# AD8232_Heart_Rate_Monitor_v10.net
KiCad netlist of a schematic drawn in EAGLE
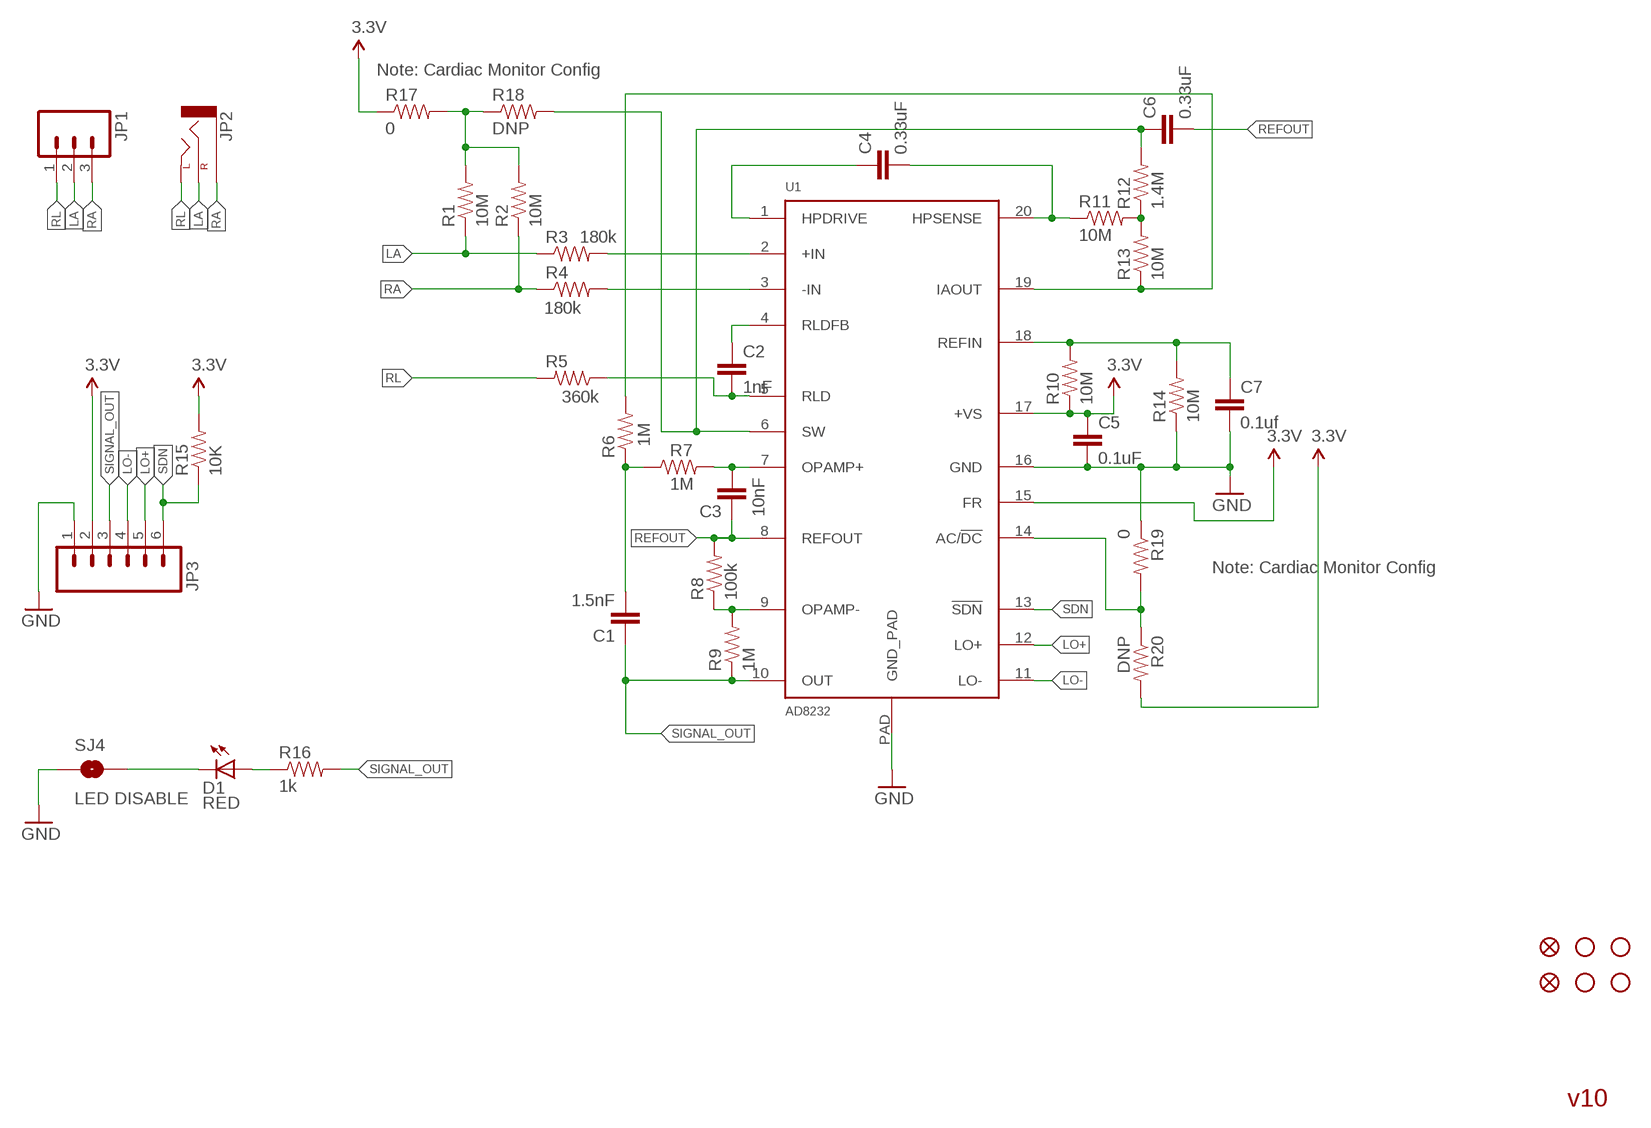
[diagram p0: schematic, sheet 1]

(export (version "E")
  (design (tool "Eeschema 10.0.6"))
  (components
    (comp (ref "C1")
      (value "1.5nF")
      (footprint "eagle-import:0603-CAP")
      (libsource (lib "eagle-import") (part "CAP0603-CAP"))
    )
    (comp (ref "C2")
      (value "1nF")
      (footprint "eagle-import:0603-CAP")
      (libsource (lib "eagle-import") (part "CAP0603-CAP"))
    )
    (comp (ref "C3")
      (value "10nF")
      (footprint "eagle-import:0603-CAP")
      (libsource (lib "eagle-import") (part "CAP0603-CAP"))
    )
    (comp (ref "C4")
      (value "0.33uF")
      (footprint "eagle-import:0805")
      (libsource (lib "eagle-import") (part "CAP0805"))
    )
    (comp (ref "C5")
      (value "0.1uF")
      (footprint "eagle-import:0603-CAP")
      (libsource (lib "eagle-import") (part "CAP0603-CAP"))
    )
    (comp (ref "C6")
      (value "0.33uF")
      (footprint "eagle-import:0805")
      (libsource (lib "eagle-import") (part "CAP0805"))
    )
    (comp (ref "C7")
      (value "0.1uf")
      (footprint "eagle-import:0603-CAP")
      (libsource (lib "eagle-import") (part "CAP0603-CAP"))
    )
    (comp (ref "D1")
      (value "RED")
      (footprint "eagle-import:LED-0603")
      (libsource (lib "eagle-import") (part "LED-RED0603"))
    )
    (comp (ref "FID1")
      (value "FIDUCIAL1X2")
      (footprint "eagle-import:FIDUCIAL-1X2")
      (libsource (lib "eagle-import") (part "FIDUCIAL1X2"))
    )
    (comp (ref "FID2")
      (value "FIDUCIAL1X2")
      (footprint "eagle-import:FIDUCIAL-1X2")
      (libsource (lib "eagle-import") (part "FIDUCIAL1X2"))
    )
    (comp (ref "JP1")
      (value "M03PTH")
      (footprint "eagle-import:1X03")
      (libsource (lib "eagle-import") (part "M03PTH"))
    )
    (comp (ref "JP2")
      (value "AUDIO-JACKSMD2")
      (footprint "eagle-import:AUDIO-JACK-3.5MM-SMD")
      (libsource (lib "eagle-import") (part "AUDIO-JACKSMD2"))
    )
    (comp (ref "JP3")
      (value "M06SIP")
      (footprint "eagle-import:1X06")
      (libsource (lib "eagle-import") (part "M06SIP"))
    )
    (comp (ref "R1")
      (value "10M")
      (footprint "eagle-import:0603-RES")
      (libsource (lib "eagle-import") (part "RESISTOR0603-RES"))
    )
    (comp (ref "R2")
      (value "10M")
      (footprint "eagle-import:0603-RES")
      (libsource (lib "eagle-import") (part "RESISTOR0603-RES"))
    )
    (comp (ref "R3")
      (value "180k")
      (footprint "eagle-import:0603-RES")
      (libsource (lib "eagle-import") (part "RESISTOR0603-RES"))
    )
    (comp (ref "R4")
      (value "180k")
      (footprint "eagle-import:0603-RES")
      (libsource (lib "eagle-import") (part "RESISTOR0603-RES"))
    )
    (comp (ref "R5")
      (value "360k")
      (footprint "eagle-import:0603-RES")
      (libsource (lib "eagle-import") (part "RESISTOR0603-RES"))
    )
    (comp (ref "R6")
      (value "1M")
      (footprint "eagle-import:0603-RES")
      (libsource (lib "eagle-import") (part "RESISTOR0603-RES"))
    )
    (comp (ref "R7")
      (value "1M")
      (footprint "eagle-import:0603-RES")
      (libsource (lib "eagle-import") (part "RESISTOR0603-RES"))
    )
    (comp (ref "R8")
      (value "100k")
      (footprint "eagle-import:0603-RES")
      (libsource (lib "eagle-import") (part "RESISTOR0603-RES"))
    )
    (comp (ref "R9")
      (value "1M")
      (footprint "eagle-import:0603-RES")
      (libsource (lib "eagle-import") (part "RESISTOR0603-RES"))
    )
    (comp (ref "R10")
      (value "10M")
      (footprint "eagle-import:0603-RES")
      (libsource (lib "eagle-import") (part "RESISTOR0603-RES"))
    )
    (comp (ref "R11")
      (value "10M")
      (footprint "eagle-import:0603-RES")
      (libsource (lib "eagle-import") (part "RESISTOR0603-RES"))
    )
    (comp (ref "R12")
      (value "1.4M")
      (footprint "eagle-import:0603-RES")
      (libsource (lib "eagle-import") (part "RESISTOR0603-RES"))
    )
    (comp (ref "R13")
      (value "10M")
      (footprint "eagle-import:0603-RES")
      (libsource (lib "eagle-import") (part "RESISTOR0603-RES"))
    )
    (comp (ref "R14")
      (value "10M")
      (footprint "eagle-import:0603-RES")
      (libsource (lib "eagle-import") (part "RESISTOR0603-RES"))
    )
    (comp (ref "R15")
      (value "10K")
      (footprint "eagle-import:0603-RES")
      (libsource (lib "eagle-import") (part "10KOHM1/10W1%(0603)0603"))
    )
    (comp (ref "R16")
      (value "1k")
      (footprint "eagle-import:0603-RES")
      (libsource (lib "eagle-import") (part "1K-1%"))
    )
    (comp (ref "R17")
      (value "0")
      (footprint "eagle-import:0603")
      (libsource (lib "eagle-import") (part "0OHM1/10W5%(0603)"))
    )
    (comp (ref "R18")
      (value "DNP")
      (footprint "eagle-import:0603")
      (libsource (lib "eagle-import") (part "0OHM1/10W5%(0603)"))
    )
    (comp (ref "R19")
      (value "0")
      (footprint "eagle-import:0603")
      (libsource (lib "eagle-import") (part "0OHM1/10W5%(0603)"))
    )
    (comp (ref "R20")
      (value "DNP")
      (footprint "eagle-import:0603")
      (libsource (lib "eagle-import") (part "0OHM1/10W5%(0603)"))
    )
    (comp (ref "SJ4")
      (value "LED DISABLE")
      (footprint "eagle-import:SJ_2S-TRACE")
      (libsource (lib "eagle-import") (part "SOLDERJUMPERTRACE"))
    )
    (comp (ref "STANDOFF1")
      (value "STAND-OFF")
      (footprint "eagle-import:STAND-OFF")
      (libsource (lib "eagle-import") (part "STAND-OFF"))
    )
    (comp (ref "STANDOFF2")
      (value "STAND-OFF")
      (footprint "eagle-import:STAND-OFF")
      (libsource (lib "eagle-import") (part "STAND-OFF"))
    )
    (comp (ref "STANDOFF3")
      (value "STAND-OFF")
      (footprint "eagle-import:STAND-OFF")
      (libsource (lib "eagle-import") (part "STAND-OFF"))
    )
    (comp (ref "STANDOFF4")
      (value "STAND-OFF")
      (footprint "eagle-import:STAND-OFF")
      (libsource (lib "eagle-import") (part "STAND-OFF"))
    )
    (comp (ref "U1")
      (value "AD8232")
      (footprint "eagle-import:LFCSP_20")
      (libsource (lib "eagle-import") (part "AD8232"))
    )
  )
  (nets
    (net (code "1") (name "3.3V") (class "Default")
      (node (ref "C5") (pin "1") (pinfunction "1_1") (pintype "passive"))
      (node (ref "JP3") (pin "2") (pinfunction "2_2") (pintype "passive"))
      (node (ref "R10") (pin "1") (pinfunction "1_1") (pintype "passive"))
      (node (ref "R15") (pin "2") (pinfunction "2_2") (pintype "passive"))
      (node (ref "R17") (pin "1") (pinfunction "1_1") (pintype "passive"))
      (node (ref "R20") (pin "2") (pinfunction "2_2") (pintype "passive"))
      (node (ref "U1") (pin "15") (pinfunction "FR_15") (pintype "bidirectional"))
      (node (ref "U1") (pin "17") (pinfunction "+VS_17") (pintype "bidirectional"))
    )
    (net (code "2") (name "GND") (class "Default")
      (node (ref "C5") (pin "2") (pinfunction "2_2") (pintype "passive"))
      (node (ref "C7") (pin "2") (pinfunction "2_2") (pintype "passive"))
      (node (ref "JP3") (pin "1") (pinfunction "1_1") (pintype "passive"))
      (node (ref "R14") (pin "1") (pinfunction "1_1") (pintype "passive"))
      (node (ref "R19") (pin "1") (pinfunction "1_1") (pintype "passive"))
      (node (ref "SJ4") (pin "1") (pinfunction "1_1") (pintype "passive"))
      (node (ref "U1") (pin "16") (pinfunction "GND_16") (pintype "bidirectional"))
      (node (ref "U1") (pin "PAD") (pinfunction "GND_PAD_PAD") (pintype "bidirectional"))
    )
    (net (code "3") (name "LA") (class "Default")
      (node (ref "JP1") (pin "2") (pinfunction "2_2") (pintype "passive"))
      (node (ref "JP2") (pin "RING") (pinfunction "RIGHT_RING") (pintype "bidirectional"))
      (node (ref "R1") (pin "1") (pinfunction "1_1") (pintype "passive"))
      (node (ref "R3") (pin "1") (pinfunction "1_1") (pintype "passive"))
    )
    (net (code "4") (name "LO+") (class "Default")
      (node (ref "JP3") (pin "5") (pinfunction "5_5") (pintype "passive"))
      (node (ref "U1") (pin "12") (pinfunction "LO+_12") (pintype "bidirectional"))
    )
    (net (code "5") (name "LO-") (class "Default")
      (node (ref "JP3") (pin "4") (pinfunction "4_4") (pintype "passive"))
      (node (ref "U1") (pin "11") (pinfunction "LO-_11") (pintype "bidirectional"))
    )
    (net (code "6") (name "Net-(C1-Pad2)") (class "Default")
      (node (ref "C1") (pin "2") (pinfunction "2_2") (pintype "passive"))
      (node (ref "R6") (pin "1") (pinfunction "1_1") (pintype "passive"))
      (node (ref "R7") (pin "1") (pinfunction "1_1") (pintype "passive"))
    )
    (net (code "7") (name "Net-(D1-PadA)") (class "Default")
      (node (ref "D1") (pin "A") (pinfunction "A_A") (pintype "passive"))
      (node (ref "R16") (pin "1") (pinfunction "1_1") (pintype "passive"))
    )
    (net (code "8") (name "Net-(D1-PadC)") (class "Default")
      (node (ref "D1") (pin "C") (pinfunction "C_C") (pintype "passive"))
      (node (ref "SJ4") (pin "2") (pinfunction "2_2") (pintype "passive"))
    )
    (net (code "9") (name "Net-(R1-Pad2)") (class "Default")
      (node (ref "R1") (pin "2") (pinfunction "2_2") (pintype "passive"))
      (node (ref "R17") (pin "2") (pinfunction "2_2") (pintype "passive"))
      (node (ref "R18") (pin "1") (pinfunction "1_1") (pintype "passive"))
      (node (ref "R2") (pin "2") (pinfunction "2_2") (pintype "passive"))
    )
    (net (code "10") (name "Net-(R11-Pad2)") (class "Default")
      (node (ref "R11") (pin "2") (pinfunction "2_2") (pintype "passive"))
      (node (ref "R12") (pin "1") (pinfunction "1_1") (pintype "passive"))
      (node (ref "R13") (pin "2") (pinfunction "2_2") (pintype "passive"))
    )
    (net (code "11") (name "Net-(U1-+IN)") (class "Default")
      (node (ref "R3") (pin "2") (pinfunction "2_2") (pintype "passive"))
      (node (ref "U1") (pin "2") (pinfunction "+IN_2") (pintype "bidirectional"))
    )
    (net (code "12") (name "Net-(U1--IN)") (class "Default")
      (node (ref "R4") (pin "2") (pinfunction "2_2") (pintype "passive"))
      (node (ref "U1") (pin "3") (pinfunction "-IN_3") (pintype "bidirectional"))
    )
    (net (code "13") (name "Net-(U1-AC{slash}~{DC})") (class "Default")
      (node (ref "R19") (pin "2") (pinfunction "2_2") (pintype "passive"))
      (node (ref "R20") (pin "1") (pinfunction "1_1") (pintype "passive"))
      (node (ref "U1") (pin "14") (pinfunction "AC/~{DC}_14") (pintype "bidirectional"))
    )
    (net (code "14") (name "Net-(U1-HPDRIVE)") (class "Default")
      (node (ref "C4") (pin "1") (pinfunction "1_1") (pintype "passive"))
      (node (ref "U1") (pin "1") (pinfunction "HPDRIVE_1") (pintype "bidirectional"))
    )
    (net (code "15") (name "Net-(U1-HPSENSE)") (class "Default")
      (node (ref "C4") (pin "2") (pinfunction "2_2") (pintype "passive"))
      (node (ref "R11") (pin "1") (pinfunction "1_1") (pintype "passive"))
      (node (ref "U1") (pin "20") (pinfunction "HPSENSE_20") (pintype "bidirectional"))
    )
    (net (code "16") (name "Net-(U1-IAOUT)") (class "Default")
      (node (ref "R13") (pin "1") (pinfunction "1_1") (pintype "passive"))
      (node (ref "R6") (pin "2") (pinfunction "2_2") (pintype "passive"))
      (node (ref "U1") (pin "19") (pinfunction "IAOUT_19") (pintype "bidirectional"))
    )
    (net (code "17") (name "Net-(U1-OPAMP+)") (class "Default")
      (node (ref "C3") (pin "2") (pinfunction "2_2") (pintype "passive"))
      (node (ref "R7") (pin "2") (pinfunction "2_2") (pintype "passive"))
      (node (ref "U1") (pin "7") (pinfunction "OPAMP+_7") (pintype "bidirectional"))
    )
    (net (code "18") (name "Net-(U1-OPAMP-)") (class "Default")
      (node (ref "R8") (pin "1") (pinfunction "1_1") (pintype "passive"))
      (node (ref "R9") (pin "2") (pinfunction "2_2") (pintype "passive"))
      (node (ref "U1") (pin "9") (pinfunction "OPAMP-_9") (pintype "bidirectional"))
    )
    (net (code "19") (name "Net-(U1-REFIN)") (class "Default")
      (node (ref "C7") (pin "1") (pinfunction "1_1") (pintype "passive"))
      (node (ref "R10") (pin "2") (pinfunction "2_2") (pintype "passive"))
      (node (ref "R14") (pin "2") (pinfunction "2_2") (pintype "passive"))
      (node (ref "U1") (pin "18") (pinfunction "REFIN_18") (pintype "bidirectional"))
    )
    (net (code "20") (name "Net-(U1-RLD)") (class "Default")
      (node (ref "C2") (pin "2") (pinfunction "2_2") (pintype "passive"))
      (node (ref "R5") (pin "1") (pinfunction "1_1") (pintype "passive"))
      (node (ref "U1") (pin "5") (pinfunction "RLD_5") (pintype "bidirectional"))
    )
    (net (code "21") (name "Net-(U1-RLDFB)") (class "Default")
      (node (ref "C2") (pin "1") (pinfunction "1_1") (pintype "passive"))
      (node (ref "U1") (pin "4") (pinfunction "RLDFB_4") (pintype "bidirectional"))
    )
    (net (code "22") (name "Net-(U1-SW)") (class "Default")
      (node (ref "C6") (pin "1") (pinfunction "1_1") (pintype "passive"))
      (node (ref "R12") (pin "2") (pinfunction "2_2") (pintype "passive"))
      (node (ref "R18") (pin "2") (pinfunction "2_2") (pintype "passive"))
      (node (ref "U1") (pin "6") (pinfunction "SW_6") (pintype "bidirectional"))
    )
    (net (code "23") (name "RA") (class "Default")
      (node (ref "JP1") (pin "3") (pinfunction "3_3") (pintype "passive"))
      (node (ref "JP2") (pin "SLEEVE") (pinfunction "SLEEVE_SLEEVE") (pintype "bidirectional"))
      (node (ref "R2") (pin "1") (pinfunction "1_1") (pintype "passive"))
      (node (ref "R4") (pin "1") (pinfunction "1_1") (pintype "passive"))
    )
    (net (code "24") (name "REFOUT") (class "Default")
      (node (ref "C3") (pin "1") (pinfunction "1_1") (pintype "passive"))
      (node (ref "C6") (pin "2") (pinfunction "2_2") (pintype "passive"))
      (node (ref "R8") (pin "2") (pinfunction "2_2") (pintype "passive"))
      (node (ref "U1") (pin "8") (pinfunction "REFOUT_8") (pintype "bidirectional"))
    )
    (net (code "25") (name "RL") (class "Default")
      (node (ref "JP1") (pin "1") (pinfunction "1_1") (pintype "passive"))
      (node (ref "JP2") (pin "TIP") (pinfunction "LEFT_TIP") (pintype "bidirectional"))
      (node (ref "R5") (pin "2") (pinfunction "2_2") (pintype "passive"))
    )
    (net (code "26") (name "SDN") (class "Default")
      (node (ref "JP3") (pin "6") (pinfunction "6_6") (pintype "passive"))
      (node (ref "R15") (pin "1") (pinfunction "1_1") (pintype "passive"))
      (node (ref "U1") (pin "13") (pinfunction "~{SDN}_13") (pintype "bidirectional"))
    )
    (net (code "27") (name "SIGNAL_OUT") (class "Default")
      (node (ref "C1") (pin "1") (pinfunction "1_1") (pintype "passive"))
      (node (ref "JP3") (pin "3") (pinfunction "3_3") (pintype "passive"))
      (node (ref "R16") (pin "2") (pinfunction "2_2") (pintype "passive"))
      (node (ref "R9") (pin "1") (pinfunction "1_1") (pintype "passive"))
      (node (ref "U1") (pin "10") (pinfunction "OUT_10") (pintype "bidirectional"))
    )
  )
)
